# Motors.net
KiCad netlist of a schematic drawn in Altium Designer
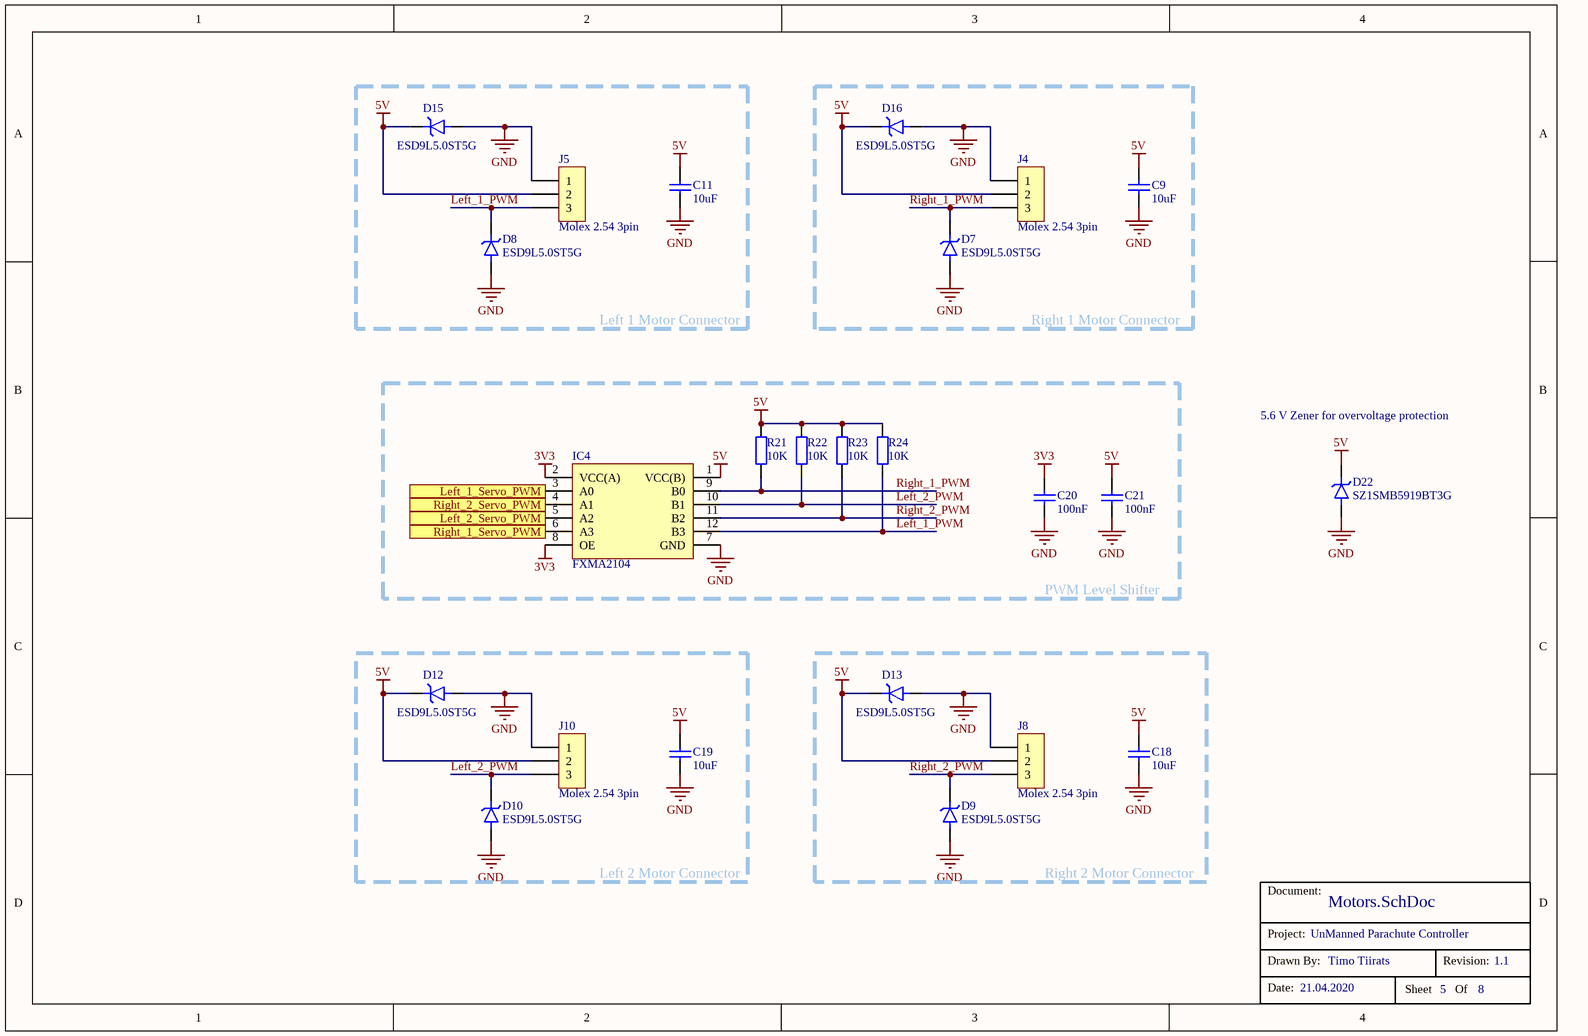
[diagram p0: Motors.SchDoc]

(export (version "E")
  (design (tool "Eeschema 10.0.6"))
  (components
    (comp (ref "C9")
      (value "10uF25V")
      (footprint "C1206 N")
      (description "Ceramic capacitor")
      (fields (field (name "CAPACITANCE") "10uF"))
      (libsource (lib "Passives") (part "Capacitor"))
    )
    (comp (ref "C11")
      (value "10uF25V")
      (footprint "C1206 N")
      (description "Ceramic capacitor")
      (fields (field (name "CAPACITANCE") "10uF"))
      (libsource (lib "Passives") (part "Capacitor"))
    )
    (comp (ref "C18")
      (value "10uF25V")
      (footprint "C1206 N")
      (description "Ceramic capacitor")
      (fields (field (name "CAPACITANCE") "10uF"))
      (libsource (lib "Passives") (part "Capacitor"))
    )
    (comp (ref "C19")
      (value "10uF25V")
      (footprint "C1206 N")
      (description "Ceramic capacitor")
      (fields (field (name "CAPACITANCE") "10uF"))
      (libsource (lib "Passives") (part "Capacitor"))
    )
    (comp (ref "C20")
      (value "100nF*V")
      (footprint "C0603 N")
      (description "Ceramic capacitor")
      (fields (field (name "CAPACITANCE") "100nF"))
      (libsource (lib "Passives") (part "Capacitor"))
    )
    (comp (ref "C21")
      (value "100nF*V")
      (footprint "C0603 N")
      (description "Ceramic capacitor")
      (fields (field (name "CAPACITANCE") "100nF"))
      (libsource (lib "Passives") (part "Capacitor"))
    )
    (comp (ref "D7")
      (value "ESD9L5.0ST5G")
      (footprint "SOD923F, NOMINAL")
      (description "TVS DIODE, Unidir, 5V/9.8V, 150mW, SOD-923, ESD9L5.0ST5G, ON SEMICONDUCTOR")
      (fields (field (name "MANUFACTURER") "ON Semiconductor"))
      (libsource (lib "Diodes") (part "ESD9L5.0ST5G"))
    )
    (comp (ref "D8")
      (value "ESD9L5.0ST5G")
      (footprint "SOD923F, NOMINAL")
      (description "TVS DIODE, Unidir, 5V/9.8V, 150mW, SOD-923, ESD9L5.0ST5G, ON SEMICONDUCTOR")
      (fields (field (name "MANUFACTURER") "ON Semiconductor"))
      (libsource (lib "Diodes") (part "ESD9L5.0ST5G"))
    )
    (comp (ref "D9")
      (value "ESD9L5.0ST5G")
      (footprint "SOD923F, NOMINAL")
      (description "TVS DIODE, Unidir, 5V/9.8V, 150mW, SOD-923, ESD9L5.0ST5G, ON SEMICONDUCTOR")
      (fields (field (name "MANUFACTURER") "ON Semiconductor"))
      (libsource (lib "Diodes") (part "ESD9L5.0ST5G"))
    )
    (comp (ref "D10")
      (value "ESD9L5.0ST5G")
      (footprint "SOD923F, NOMINAL")
      (description "TVS DIODE, Unidir, 5V/9.8V, 150mW, SOD-923, ESD9L5.0ST5G, ON SEMICONDUCTOR")
      (fields (field (name "MANUFACTURER") "ON Semiconductor"))
      (libsource (lib "Diodes") (part "ESD9L5.0ST5G"))
    )
    (comp (ref "D12")
      (value "ESD9L5.0ST5G")
      (footprint "SOD923F, NOMINAL")
      (description "TVS DIODE, Unidir, 5V/9.8V, 150mW, SOD-923, ESD9L5.0ST5G, ON SEMICONDUCTOR")
      (fields (field (name "MANUFACTURER") "ON Semiconductor"))
      (libsource (lib "Diodes") (part "ESD9L5.0ST5G"))
    )
    (comp (ref "D13")
      (value "ESD9L5.0ST5G")
      (footprint "SOD923F, NOMINAL")
      (description "TVS DIODE, Unidir, 5V/9.8V, 150mW, SOD-923, ESD9L5.0ST5G, ON SEMICONDUCTOR")
      (fields (field (name "MANUFACTURER") "ON Semiconductor"))
      (libsource (lib "Diodes") (part "ESD9L5.0ST5G"))
    )
    (comp (ref "D15")
      (value "ESD9L5.0ST5G")
      (footprint "SOD923F, NOMINAL")
      (description "TVS DIODE, Unidir, 5V/9.8V, 150mW, SOD-923, ESD9L5.0ST5G, ON SEMICONDUCTOR")
      (fields (field (name "MANUFACTURER") "ON Semiconductor"))
      (libsource (lib "Diodes") (part "ESD9L5.0ST5G"))
    )
    (comp (ref "D16")
      (value "ESD9L5.0ST5G")
      (footprint "SOD923F, NOMINAL")
      (description "TVS DIODE, Unidir, 5V/9.8V, 150mW, SOD-923, ESD9L5.0ST5G, ON SEMICONDUCTOR")
      (fields (field (name "MANUFACTURER") "ON Semiconductor"))
      (libsource (lib "Diodes") (part "ESD9L5.0ST5G"))
    )
    (comp (ref "D22")
      (value "SZ1SMB5919BT3G")
      (footprint "DO-214, NOMINAL")
      (description "ZENER, 5.1V, 3W, SOD-123, ON SEMICONDUCTOR, SZ1SMB5918BT3G")
      (libsource (lib "Diodes") (part "SZ1SMB5918BT3G"))
    )
    (comp (ref "IC4")
      (value "FXMA2104")
      (footprint "QFN12 1.8x1.8, NOMINAL")
      (description "Level shifter, 4 inputs, 1.65 .. 5.5Vin, 3ns delay, FXMA2104, ON SEMICONDUCTOR")
      (libsource (lib "LevelShifters") (part "FXMA2104"))
    )
    (comp (ref "J4")
      (value "Molex 2.54 3pin")
      (footprint "22-27-2031")
      (description "Molex header, 3 pin, KK 6410 series")
      (fields (field (name "MANUFACTURER PART NUMBER") "22-27-2031"))
      (libsource (lib "molex_kk") (part "Molex header, 3 pin, KK 6410 series"))
    )
    (comp (ref "J5")
      (value "Molex 2.54 3pin")
      (footprint "22-27-2031")
      (description "Molex header, 3 pin, KK 6410 series")
      (fields (field (name "MANUFACTURER PART NUMBER") "22-27-2031"))
      (libsource (lib "molex_kk") (part "Molex header, 3 pin, KK 6410 series"))
    )
    (comp (ref "J8")
      (value "Molex 2.54 3pin")
      (footprint "22-27-2031")
      (description "Molex header, 3 pin, KK 6410 series")
      (fields (field (name "MANUFACTURER PART NUMBER") "22-27-2031"))
      (libsource (lib "molex_kk") (part "Molex header, 3 pin, KK 6410 series"))
    )
    (comp (ref "J10")
      (value "Molex 2.54 3pin")
      (footprint "22-27-2031")
      (description "Molex header, 3 pin, KK 6410 series")
      (fields (field (name "MANUFACTURER PART NUMBER") "22-27-2031"))
      (libsource (lib "molex_kk") (part "Molex header, 3 pin, KK 6410 series"))
    )
    (comp (ref "R21")
      (value "10K")
      (footprint "R0603")
      (description "Resistor")
      (fields (field (name "RESISTANCE") "10K"))
      (libsource (lib "Passives") (part "Resistor"))
    )
    (comp (ref "R22")
      (value "10K")
      (footprint "R0603")
      (description "Resistor")
      (fields (field (name "RESISTANCE") "10K"))
      (libsource (lib "Passives") (part "Resistor"))
    )
    (comp (ref "R23")
      (value "10K")
      (footprint "R0603")
      (description "Resistor")
      (fields (field (name "RESISTANCE") "10K"))
      (libsource (lib "Passives") (part "Resistor"))
    )
    (comp (ref "R24")
      (value "10K")
      (footprint "R0603")
      (description "Resistor")
      (fields (field (name "RESISTANCE") "10K"))
      (libsource (lib "Passives") (part "Resistor"))
    )
  )
  (nets
    (net (code "1") (name "/Left_1_PWM") (class "Default")
      (node (ref "D8") (pin "C") (pinfunction "C_C") (pintype "passive"))
      (node (ref "IC4") (pin "12") (pinfunction "B3_12") (pintype "passive"))
      (node (ref "J5") (pin "3") (pinfunction "3_3") (pintype "passive"))
      (node (ref "R24") (pin "1") (pinfunction "1_1") (pintype "passive"))
    )
    (net (code "2") (name "/Left_1_Servo_PWM") (class "Default")
      (node (ref "IC4") (pin "3") (pinfunction "A0_3") (pintype "passive"))
    )
    (net (code "3") (name "/Left_2_PWM") (class "Default")
      (node (ref "D10") (pin "C") (pinfunction "C_C") (pintype "passive"))
      (node (ref "IC4") (pin "10") (pinfunction "B1_10") (pintype "passive"))
      (node (ref "J10") (pin "3") (pinfunction "3_3") (pintype "passive"))
      (node (ref "R22") (pin "1") (pinfunction "1_1") (pintype "passive"))
    )
    (net (code "4") (name "/Left_2_Servo_PWM") (class "Default")
      (node (ref "IC4") (pin "5") (pinfunction "A2_5") (pintype "passive"))
    )
    (net (code "5") (name "/Right_1_PWM") (class "Default")
      (node (ref "D7") (pin "C") (pinfunction "C_C") (pintype "passive"))
      (node (ref "IC4") (pin "9") (pinfunction "B0_9") (pintype "passive"))
      (node (ref "J4") (pin "3") (pinfunction "3_3") (pintype "passive"))
      (node (ref "R21") (pin "1") (pinfunction "1_1") (pintype "passive"))
    )
    (net (code "6") (name "/Right_1_Servo_PWM") (class "Default")
      (node (ref "IC4") (pin "6") (pinfunction "A3_6") (pintype "passive"))
    )
    (net (code "7") (name "/Right_2_PWM") (class "Default")
      (node (ref "D9") (pin "C") (pinfunction "C_C") (pintype "passive"))
      (node (ref "IC4") (pin "11") (pinfunction "B2_11") (pintype "passive"))
      (node (ref "J8") (pin "3") (pinfunction "3_3") (pintype "passive"))
      (node (ref "R23") (pin "1") (pinfunction "1_1") (pintype "passive"))
    )
    (net (code "8") (name "/Right_2_Servo_PWM") (class "Default")
      (node (ref "IC4") (pin "4") (pinfunction "A1_4") (pintype "passive"))
    )
    (net (code "9") (name "3V3") (class "Default")
      (node (ref "C20") (pin "2") (pinfunction "2_2") (pintype "passive"))
      (node (ref "IC4") (pin "2") (pinfunction "VCC(A)_2") (pintype "passive"))
      (node (ref "IC4") (pin "8") (pinfunction "OE_8") (pintype "passive"))
    )
    (net (code "10") (name "5V") (class "Default")
      (node (ref "C11") (pin "2") (pinfunction "2_2") (pintype "passive"))
      (node (ref "C18") (pin "2") (pinfunction "2_2") (pintype "passive"))
      (node (ref "C19") (pin "2") (pinfunction "2_2") (pintype "passive"))
      (node (ref "C21") (pin "2") (pinfunction "2_2") (pintype "passive"))
      (node (ref "C9") (pin "2") (pinfunction "2_2") (pintype "passive"))
      (node (ref "D12") (pin "C") (pinfunction "C_C") (pintype "passive"))
      (node (ref "D13") (pin "C") (pinfunction "C_C") (pintype "passive"))
      (node (ref "D15") (pin "C") (pinfunction "C_C") (pintype "passive"))
      (node (ref "D16") (pin "C") (pinfunction "C_C") (pintype "passive"))
      (node (ref "D22") (pin "C") (pinfunction "C_C") (pintype "passive"))
      (node (ref "IC4") (pin "1") (pinfunction "VCC(B)_1") (pintype "passive"))
      (node (ref "J10") (pin "2") (pinfunction "2_2") (pintype "passive"))
      (node (ref "J4") (pin "2") (pinfunction "2_2") (pintype "passive"))
      (node (ref "J5") (pin "2") (pinfunction "2_2") (pintype "passive"))
      (node (ref "J8") (pin "2") (pinfunction "2_2") (pintype "passive"))
      (node (ref "R21") (pin "2") (pinfunction "2_2") (pintype "passive"))
      (node (ref "R22") (pin "2") (pinfunction "2_2") (pintype "passive"))
      (node (ref "R23") (pin "2") (pinfunction "2_2") (pintype "passive"))
      (node (ref "R24") (pin "2") (pinfunction "2_2") (pintype "passive"))
    )
    (net (code "11") (name "GND") (class "Default")
      (node (ref "C11") (pin "1") (pinfunction "1_1") (pintype "passive"))
      (node (ref "C18") (pin "1") (pinfunction "1_1") (pintype "passive"))
      (node (ref "C19") (pin "1") (pinfunction "1_1") (pintype "passive"))
      (node (ref "C20") (pin "1") (pinfunction "1_1") (pintype "passive"))
      (node (ref "C21") (pin "1") (pinfunction "1_1") (pintype "passive"))
      (node (ref "C9") (pin "1") (pinfunction "1_1") (pintype "passive"))
      (node (ref "D10") (pin "A") (pinfunction "A_A") (pintype "passive"))
      (node (ref "D12") (pin "A") (pinfunction "A_A") (pintype "passive"))
      (node (ref "D13") (pin "A") (pinfunction "A_A") (pintype "passive"))
      (node (ref "D15") (pin "A") (pinfunction "A_A") (pintype "passive"))
      (node (ref "D16") (pin "A") (pinfunction "A_A") (pintype "passive"))
      (node (ref "D22") (pin "A") (pinfunction "A_A") (pintype "passive"))
      (node (ref "D7") (pin "A") (pinfunction "A_A") (pintype "passive"))
      (node (ref "D8") (pin "A") (pinfunction "A_A") (pintype "passive"))
      (node (ref "D9") (pin "A") (pinfunction "A_A") (pintype "passive"))
      (node (ref "IC4") (pin "7") (pinfunction "GND_7") (pintype "passive"))
      (node (ref "J10") (pin "1") (pinfunction "1_1") (pintype "passive"))
      (node (ref "J4") (pin "1") (pinfunction "1_1") (pintype "passive"))
      (node (ref "J5") (pin "1") (pinfunction "1_1") (pintype "passive"))
      (node (ref "J8") (pin "1") (pinfunction "1_1") (pintype "passive"))
    )
  )
)
